# FLASH.net
KiCad netlist of a schematic drawn in Altium Designer
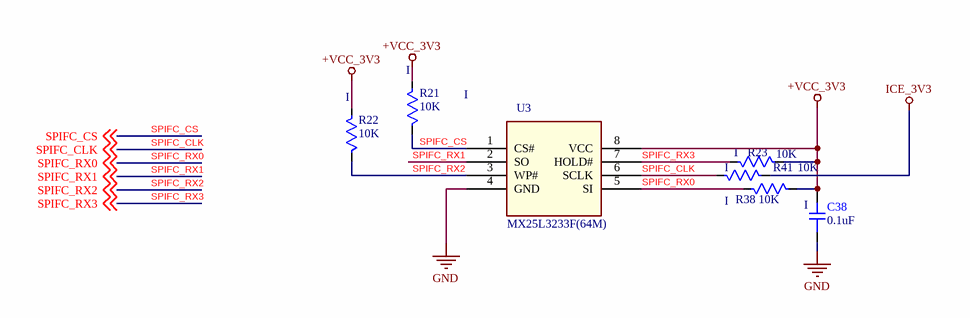
[diagram p0: FLASH.SchDoc]

(export (version "E")
  (design (tool "Eeschema 10.0.6"))
  (components
    (comp (ref "C38")
      (value "0.1uF")
      (footprint "C0402")
      (fields (field (name "BOM") "I"))
      (libsource (lib "AMIDA7") (part "Cap"))
    )
    (comp (ref "R21")
      (value "10K")
      (footprint "R0402")
      (fields (field (name "BOM") "I"))
      (libsource (lib "AMIDA7") (part "Res"))
    )
    (comp (ref "R22")
      (value "10K")
      (footprint "R0402")
      (fields (field (name "BOM") "I"))
      (libsource (lib "AMIDA7") (part "Res"))
    )
    (comp (ref "R23")
      (value "10K")
      (footprint "R0402")
      (fields (field (name "BOM") "I"))
      (libsource (lib "AMIDA7") (part "Res"))
    )
    (comp (ref "R38")
      (value "10K")
      (footprint "R0402")
      (fields (field (name "BOM") "I"))
      (libsource (lib "AMIDA7") (part "Res"))
    )
    (comp (ref "R41")
      (value "10K")
      (footprint "R0402")
      (fields (field (name "BOM") "I"))
      (libsource (lib "AMIDA7") (part "Res"))
    )
    (comp (ref "U3")
      (value "MX25L3233F(64M)")
      (footprint "SOIC127P790X216-8N(MX25L3233F)")
      (description "MX25L3233F(32M)")
      (fields (field (name "BOM") "I"))
      (libsource (lib "AMIDA7") (part "SOP-8"))
    )
  )
  (nets
    (net (code "1") (name "+VCC_3V3") (class "Default")
      (node (ref "C38") (pin "2") (pinfunction "2_2") (pintype "passive"))
      (node (ref "R21") (pin "2") (pinfunction "2_2") (pintype "passive"))
      (node (ref "R22") (pin "2") (pinfunction "2_2") (pintype "passive"))
      (node (ref "R23") (pin "1") (pinfunction "1_1") (pintype "passive"))
      (node (ref "R38") (pin "1") (pinfunction "1_1") (pintype "passive"))
      (node (ref "U3") (pin "8") (pinfunction "VCC_8") (pintype "passive"))
    )
    (net (code "2") (name "GND") (class "Default")
      (node (ref "C38") (pin "1") (pinfunction "1_1") (pintype "passive"))
      (node (ref "U3") (pin "4") (pinfunction "GND_4") (pintype "passive"))
    )
    (net (code "3") (name "ICE_3V3") (class "Default")
      (node (ref "R41") (pin "1") (pinfunction "1_1") (pintype "passive"))
    )
    (net (code "4") (name "SPIFC_CLK") (class "Default")
      (node (ref "R41") (pin "2") (pinfunction "2_2") (pintype "passive"))
      (node (ref "U3") (pin "6") (pinfunction "SCLK_6") (pintype "passive"))
    )
    (net (code "5") (name "SPIFC_CS") (class "Default")
      (node (ref "R21") (pin "1") (pinfunction "1_1") (pintype "passive"))
      (node (ref "U3") (pin "1") (pinfunction "CS#_1") (pintype "passive"))
    )
    (net (code "6") (name "SPIFC_RX0") (class "Default")
      (node (ref "R38") (pin "2") (pinfunction "2_2") (pintype "passive"))
      (node (ref "U3") (pin "5") (pinfunction "SI_5") (pintype "passive"))
    )
    (net (code "7") (name "SPIFC_RX1") (class "Default")
      (node (ref "U3") (pin "2") (pinfunction "SO_2") (pintype "passive"))
    )
    (net (code "8") (name "SPIFC_RX2") (class "Default")
      (node (ref "R22") (pin "1") (pinfunction "1_1") (pintype "passive"))
      (node (ref "U3") (pin "3") (pinfunction "WP#_3") (pintype "passive"))
    )
    (net (code "9") (name "SPIFC_RX3") (class "Default")
      (node (ref "R23") (pin "2") (pinfunction "2_2") (pintype "passive"))
      (node (ref "U3") (pin "7") (pinfunction "HOLD#_7") (pintype "passive"))
    )
  )
)
